# SCH_Business-Card_2026-10-04.net
KiCad netlist of a schematic drawn in EasyEDA
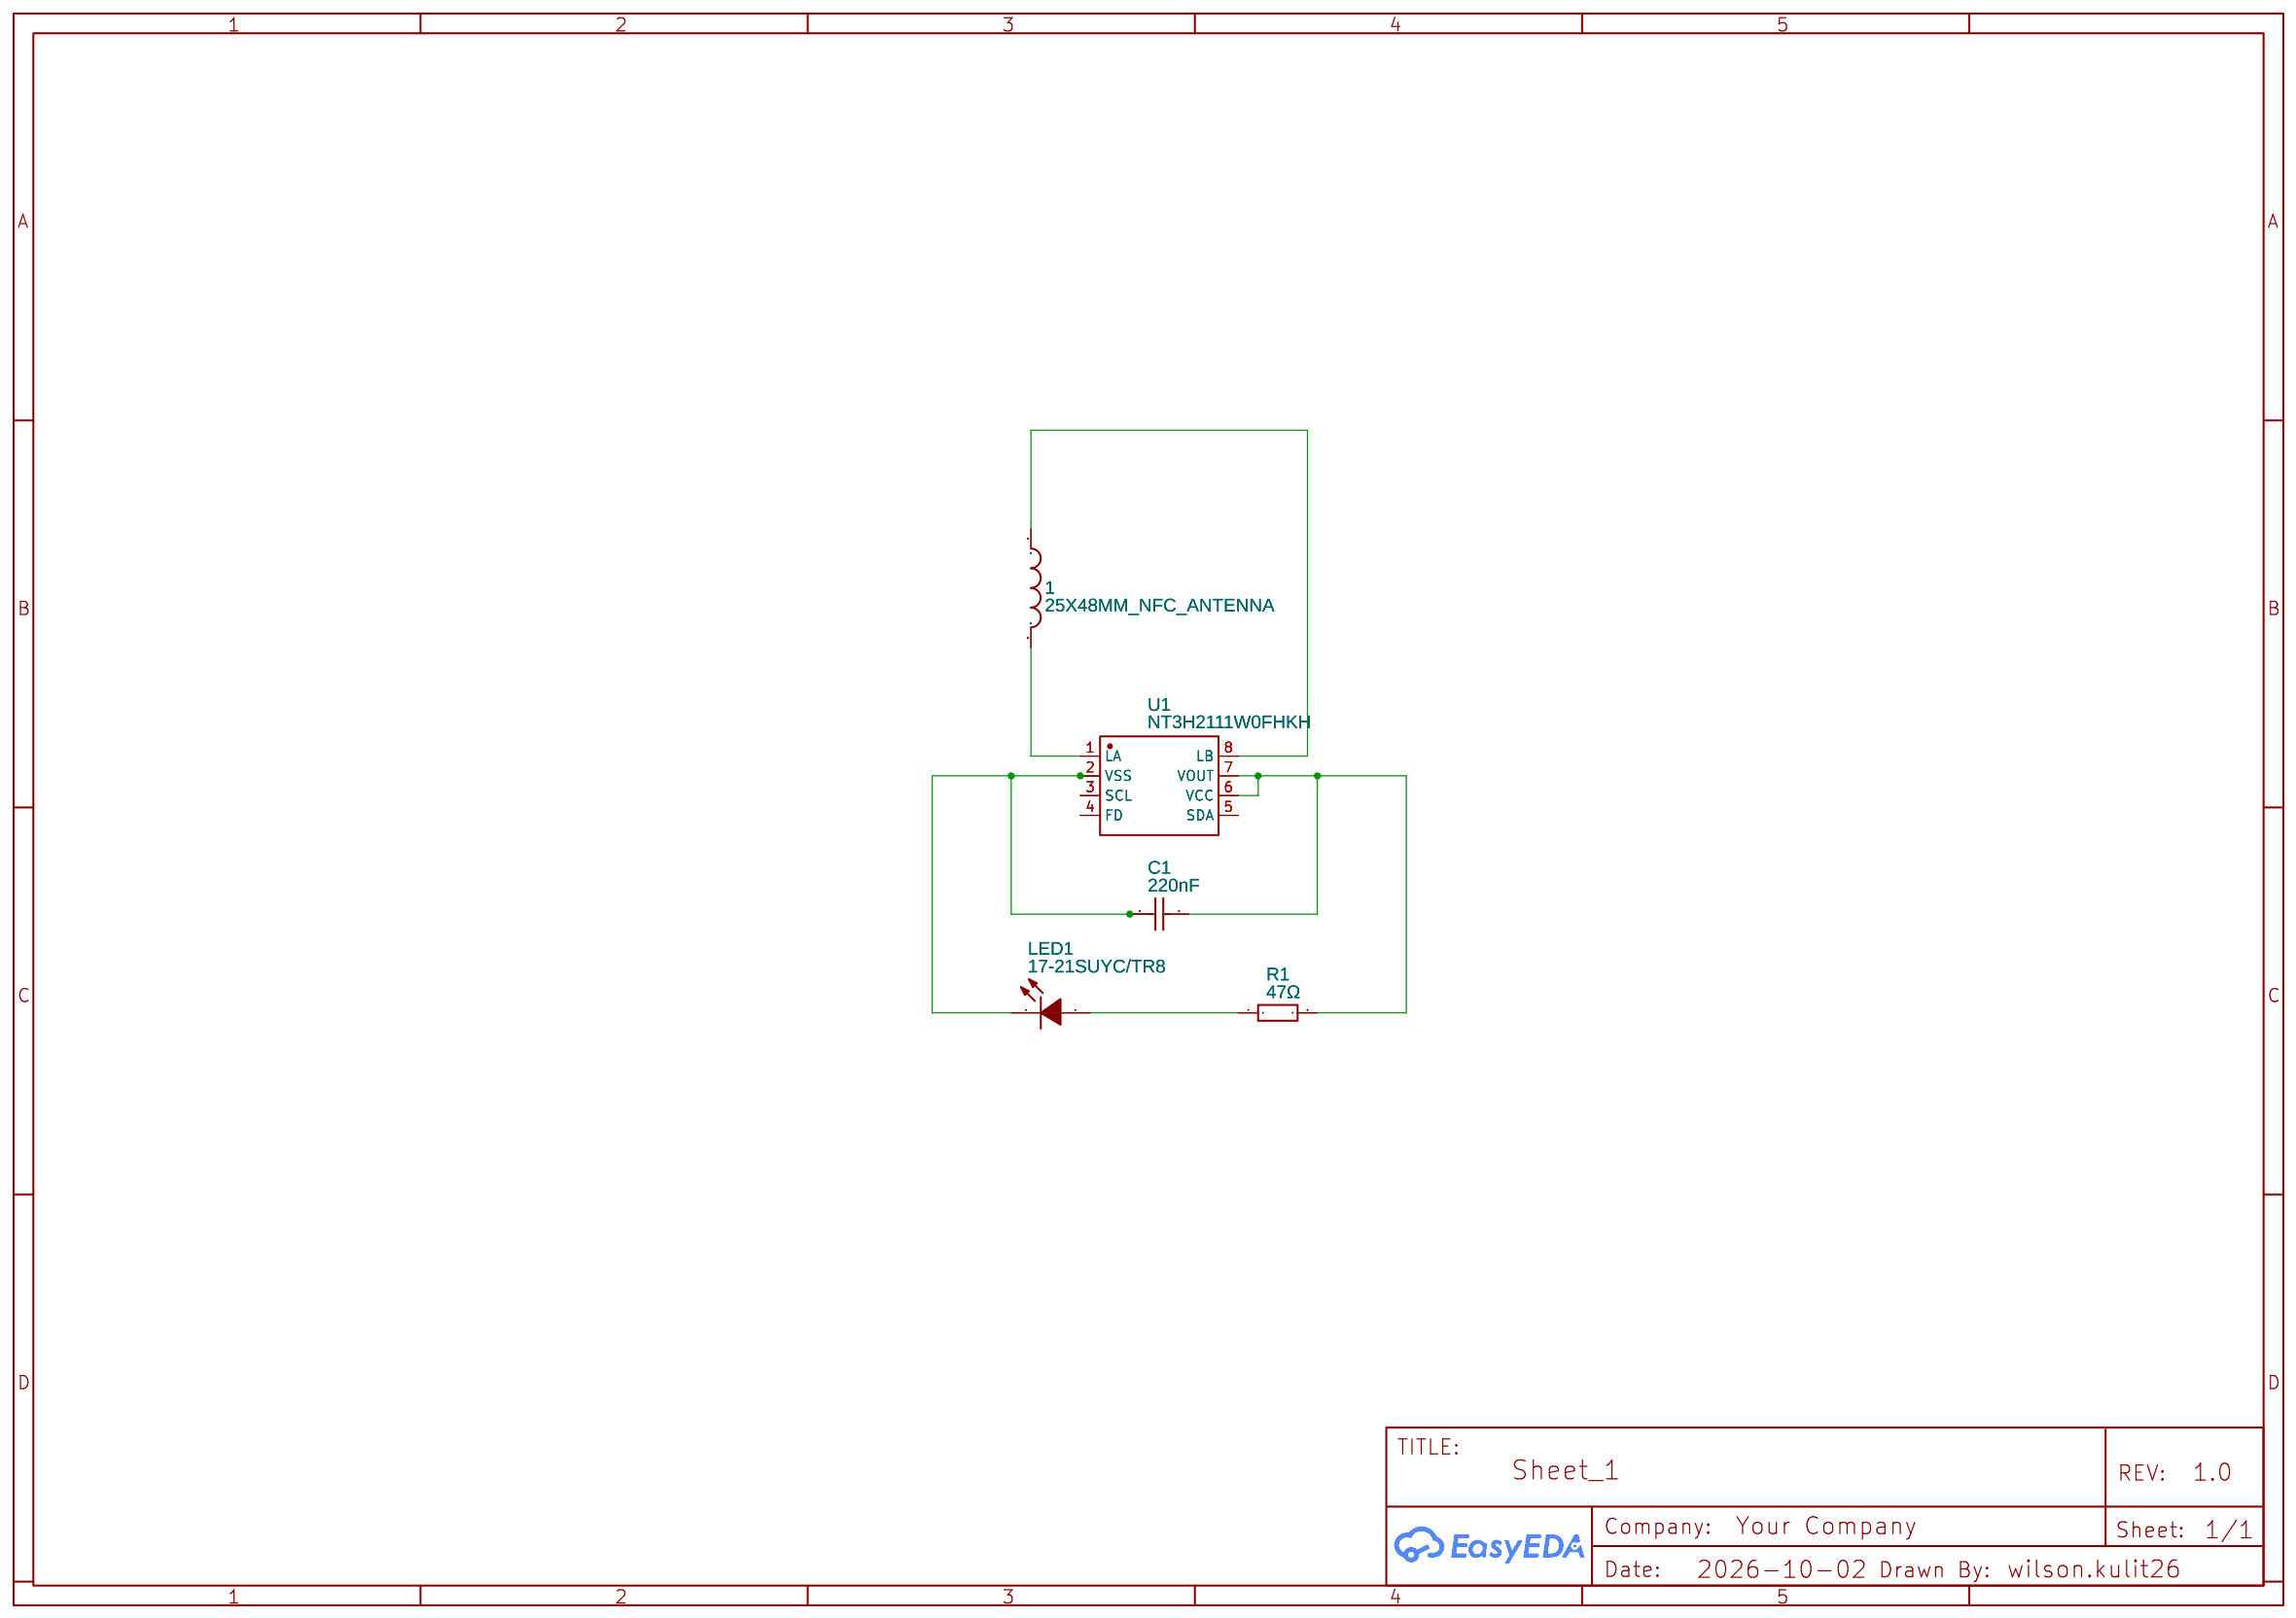
[diagram p0: schematic sheet]

(export (version "E")
  (design (tool "Eeschema 10.0.6"))
  (components
    (comp (ref "1") (value "25X48MM_NFC_ANTENNA") (libsource (lib "") (part "25X48MM_NFC_ANTENNA")))
    (comp (ref "C1")
      (value "220nF")
      (fields
        (field (name "Manufacturer Part") "CL10B224KA8NNNC")
        (field (name "Manufacturer") "SAMSUNG(三星)")
      )
      (libsource (lib "") (part "CL10B224KA8NNNC"))
    )
    (comp (ref "LED1")
      (value "17-21SUYC/TR8")
      (fields (field (name "Manufacturer Part") "KT-0805黄灯") (field (name "Manufacturer") "KENTO"))
      (libsource (lib "") (part "17-21SUYC/TR8"))
    )
    (comp (ref "R1")
      (value "47Ω")
      (fields
        (field (name "Manufacturer Part") "0603WAF470JT5E")
        (field (name "Manufacturer") "UNI-ROYAL(厚声)")
      )
      (libsource (lib "") (part "0603WAF470JT5E"))
    )
    (comp (ref "U1")
      (value "NT3H2111W0FHKH")
      (fields (field (name "Manufacturer") "NXP(恩智浦)"))
      (libsource (lib "") (part "NT3H2111W0FHKH"))
    )
  )
  (nets
    (net (code "1") (name "Net-(LED1-+)") (class "Default")
      (node (ref "LED1") (pin "1") (pinfunction "+_1") (pintype "unspecified"))
      (node (ref "R1") (pin "1") (pinfunction "1_1") (pintype "input"))
    )
    (net (code "2") (name "Net-(LED1--)") (class "Default")
      (node (ref "C1") (pin "1") (pinfunction "1_1") (pintype "input"))
      (node (ref "LED1") (pin "2") (pinfunction "-_2") (pintype "unspecified"))
      (node (ref "U1") (pin "2") (pinfunction "VSS_2") (pintype "unspecified"))
    )
    (net (code "3") (name "Net-(U1-LA)") (class "Default")
      (node (ref "1") (pin "P$2") (pinfunction "P$2_P$2") (pintype "bidirectional"))
      (node (ref "U1") (pin "1") (pinfunction "LA_1") (pintype "unspecified"))
    )
    (net (code "4") (name "Net-(U1-LB)") (class "Default")
      (node (ref "1") (pin "P$1") (pinfunction "P$1_P$1") (pintype "bidirectional"))
      (node (ref "U1") (pin "8") (pinfunction "LB_8") (pintype "unspecified"))
    )
    (net (code "5") (name "Net-(U1-VCC)") (class "Default")
      (node (ref "C1") (pin "2") (pinfunction "2_2") (pintype "input"))
      (node (ref "R1") (pin "2") (pinfunction "2_2") (pintype "input"))
      (node (ref "U1") (pin "6") (pinfunction "VCC_6") (pintype "unspecified"))
      (node (ref "U1") (pin "7") (pinfunction "VOUT_7") (pintype "unspecified"))
    )
    (net (code "6") (name "unconnected-(U1-FD-Pad4)") (class "Default")
      (node (ref "U1") (pin "4") (pinfunction "FD_4") (pintype "unspecified"))
    )
    (net (code "7") (name "unconnected-(U1-SCL-Pad3)") (class "Default")
      (node (ref "U1") (pin "3") (pinfunction "SCL_3") (pintype "unspecified"))
    )
    (net (code "8") (name "unconnected-(U1-SDA-Pad5)") (class "Default")
      (node (ref "U1") (pin "5") (pinfunction "SDA_5") (pintype "unspecified"))
    )
  )
)
